# PIC32.net
KiCad netlist of a schematic drawn in Altium Designer
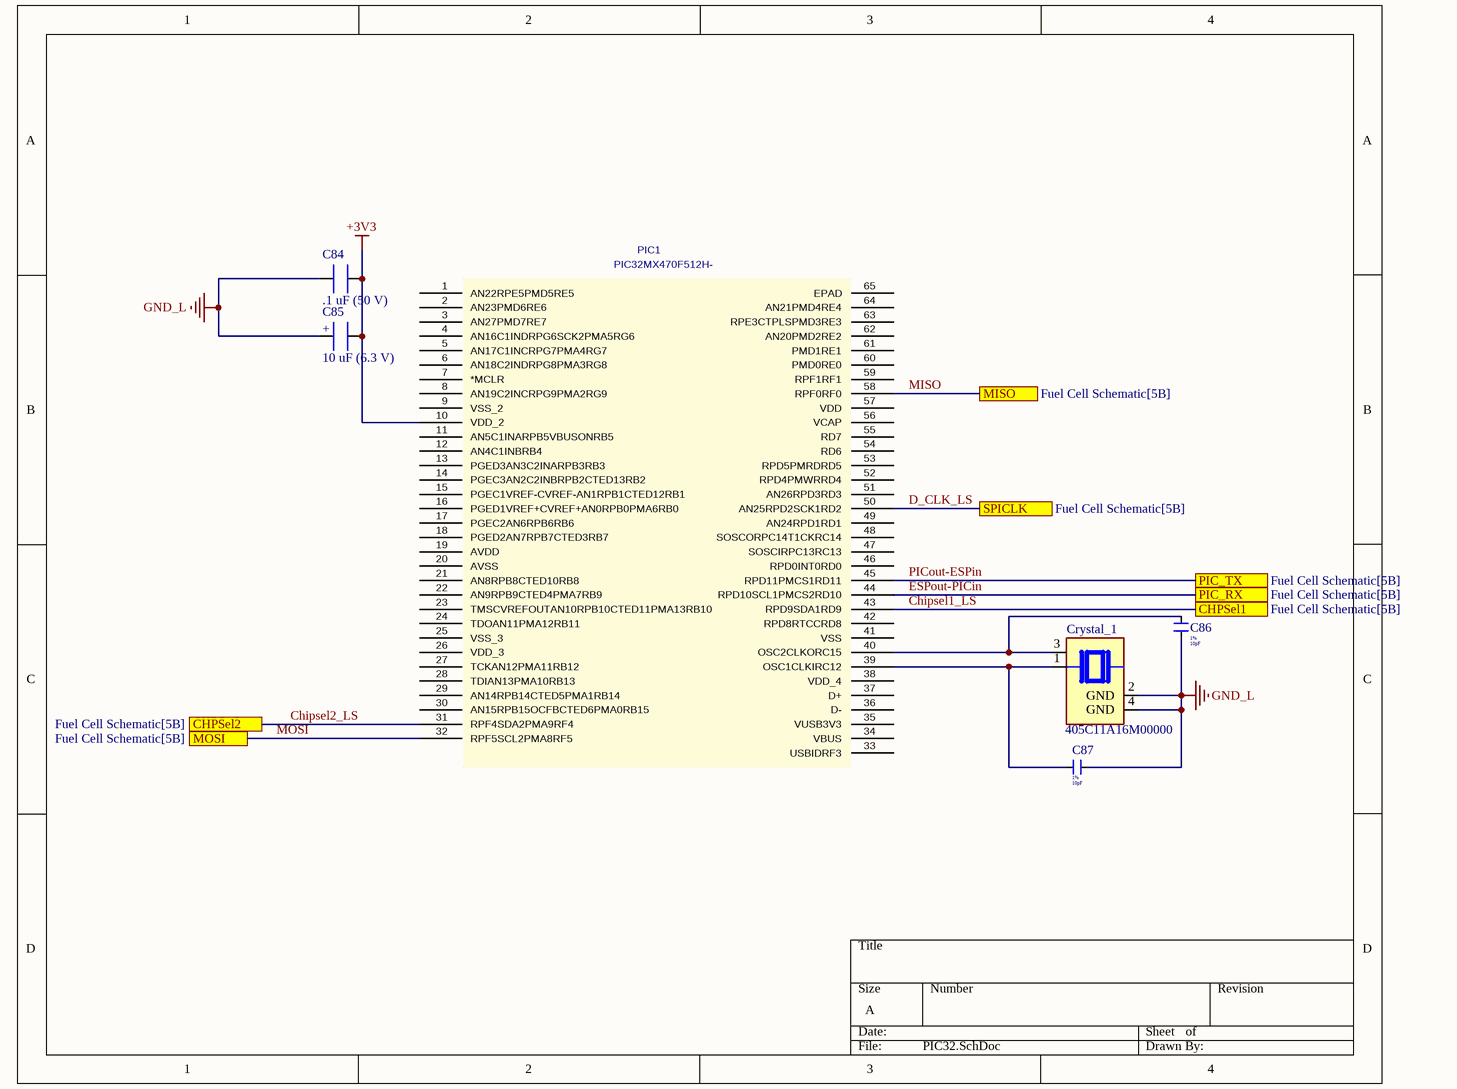
[diagram p0: PIC32.SchDoc]

(export (version "E")
  (design (tool "Eeschema 10.0.6"))
  (components
    (comp (ref "C84")
      (value ".1 uF (50 V)")
      (footprint ".1uF capacitor")
      (libsource (lib "Schlib1") (part ".1 uF cap"))
    )
    (comp (ref "C85")
      (value "10 uF (6.3 V)")
      (footprint "10 uF cap")
      (libsource (lib "Schlib1") (part "10 uF cap"))
    )
    (comp (ref "C86")
      (value "~")
      (footprint "Kemet_10pF_0805")
      (description "Cap, AEC-Q200, 10PF, 50V, Mlcc, 0805;")
      (fields
        (field (name "MANUFACTURER") "KEMET")
        (field (name "MANUFACTURER PART NUMBER") "C0805C100F5GACAUTO")
        (field (name "TOLLERANCE") "1%")
        (field (name "CAPACITANCE") "10pF")
      )
      (libsource (lib "Schlib1") (part "C0805C100F5GACAUTO"))
    )
    (comp (ref "C87")
      (value "~")
      (footprint "Kemet_10pF_0805")
      (description "Cap, AEC-Q200, 10PF, 50V, Mlcc, 0805;")
      (fields
        (field (name "MANUFACTURER") "KEMET")
        (field (name "MANUFACTURER PART NUMBER") "C0805C100F5GACAUTO")
        (field (name "TOLLERANCE") "1%")
        (field (name "CAPACITANCE") "10pF")
      )
      (libsource (lib "Schlib1") (part "C0805C100F5GACAUTO"))
    )
    (comp (ref "Crystal_1")
      (value "405C11A16M00000")
      (footprint "XTAL_405C11A16M00000")
      (description "CRYSTAL 16.0000MHZ 10PF SMD")
      (fields
        (field (name "DIGI-KEY_PART_NUMBER") "CTX834TR-ND")
        (field (name "MF") "CTS-Frequency Controls")
      )
      (libsource (lib "Schlib1") (part "405C11A16M00000"))
    )
    (comp (ref "PIC1")
      (value "PIC32MX470F512H-")
      (footprint "Quad64")
      (fields
        (field (name "MANUFACTURER_PART_NUMBER") "PIC32MX470F512H-I/MR")
        (field (name "COPYRIGHT") "Copyright (C) 2023 Ultra Librarian. All rights reserved.")
      )
      (libsource (lib "Schlib1") (part "PIC32MX470F512H-"))
    )
  )
  (nets
    (net (code "1") (name "+3V3") (class "Default")
      (node (ref "C84") (pin "2") (pinfunction "2_2") (pintype "passive"))
      (node (ref "C85") (pin "2") (pinfunction "2_2") (pintype "passive"))
      (node (ref "PIC1") (pin "10") (pinfunction "VDD_2_10") (pintype "passive"))
    )
    (net (code "2") (name "/Chipsel1_LS") (class "Default")
      (node (ref "PIC1") (pin "43") (pinfunction "RPD9SDA1RD9_43") (pintype "passive"))
    )
    (net (code "3") (name "/Chipsel2_LS") (class "Default")
      (node (ref "PIC1") (pin "31") (pinfunction "RPF4SDA2PMA9RF4_31") (pintype "passive"))
    )
    (net (code "4") (name "/D_CLK_LS") (class "Default")
      (node (ref "PIC1") (pin "50") (pinfunction "AN25RPD2SCK1RD2_50") (pintype "passive"))
    )
    (net (code "5") (name "/ESPout-PICin") (class "Default")
      (node (ref "PIC1") (pin "44") (pinfunction "RPD10SCL1PMCS2RD10_44") (pintype "passive"))
    )
    (net (code "6") (name "/MISO") (class "Default")
      (node (ref "PIC1") (pin "58") (pinfunction "RPF0RF0_58") (pintype "passive"))
    )
    (net (code "7") (name "/MOSI") (class "Default")
      (node (ref "PIC1") (pin "32") (pinfunction "RPF5SCL2PMA8RF5_32") (pintype "passive"))
    )
    (net (code "8") (name "/PICout-ESPin") (class "Default")
      (node (ref "PIC1") (pin "45") (pinfunction "RPD11PMCS1RD11_45") (pintype "passive"))
    )
    (net (code "9") (name "GND_L") (class "Default")
      (node (ref "C84") (pin "1") (pinfunction "1_1") (pintype "passive"))
      (node (ref "C85") (pin "1") (pinfunction "1_1") (pintype "passive"))
      (node (ref "C86") (pin "2") (pinfunction "2_2") (pintype "passive"))
      (node (ref "C87") (pin "1") (pinfunction "1_1") (pintype "passive"))
      (node (ref "Crystal_1") (pin "2") (pinfunction "GND_2") (pintype "power_in"))
      (node (ref "Crystal_1") (pin "4") (pinfunction "GND_4") (pintype "power_in"))
    )
    (net (code "10") (name "Net-(Crystal_1-2)") (class "Default")
      (node (ref "C86") (pin "1") (pinfunction "1_1") (pintype "passive"))
      (node (ref "Crystal_1") (pin "3") (pinfunction "2_3") (pintype "passive"))
      (node (ref "PIC1") (pin "40") (pinfunction "OSC2CLKORC15_40") (pintype "passive"))
    )
    (net (code "11") (name "Net-(PIC1-OSC1CLKIRC12)") (class "Default")
      (node (ref "C87") (pin "2") (pinfunction "2_2") (pintype "passive"))
      (node (ref "Crystal_1") (pin "1") (pinfunction "1_1") (pintype "passive"))
      (node (ref "PIC1") (pin "39") (pinfunction "OSC1CLKIRC12_39") (pintype "passive"))
    )
    (net (code "12") (name "unconnected-(PIC1-*MCLR-Pad7)") (class "Default")
      (node (ref "PIC1") (pin "7") (pinfunction "*MCLR_7") (pintype "passive"))
    )
    (net (code "13") (name "unconnected-(PIC1-AN4C1INBRB4-Pad12)") (class "Default")
      (node (ref "PIC1") (pin "12") (pinfunction "AN4C1INBRB4_12") (pintype "passive"))
    )
    (net (code "14") (name "unconnected-(PIC1-AN5C1INARPB5VBUSONRB5-Pad11)") (class "Default")
      (node (ref "PIC1") (pin "11") (pinfunction "AN5C1INARPB5VBUSONRB5_11") (pintype "passive"))
    )
    (net (code "15") (name "unconnected-(PIC1-AN8RPB8CTED10RB8-Pad21)") (class "Default")
      (node (ref "PIC1") (pin "21") (pinfunction "AN8RPB8CTED10RB8_21") (pintype "passive"))
    )
    (net (code "16") (name "unconnected-(PIC1-AN9RPB9CTED4PMA7RB9-Pad22)") (class "Default")
      (node (ref "PIC1") (pin "22") (pinfunction "AN9RPB9CTED4PMA7RB9_22") (pintype "passive"))
    )
    (net (code "17") (name "unconnected-(PIC1-AN14RPB14CTED5PMA1RB14-Pad29)") (class "Default")
      (node (ref "PIC1") (pin "29") (pinfunction "AN14RPB14CTED5PMA1RB14_29") (pintype "passive"))
    )
    (net (code "18") (name "unconnected-(PIC1-AN15RPB15OCFBCTED6PMA0RB15-Pad30)") (class "Default")
      (node (ref "PIC1") (pin "30") (pinfunction "AN15RPB15OCFBCTED6PMA0RB15_30") (pintype "passive"))
    )
    (net (code "19") (name "unconnected-(PIC1-AN16C1INDRPG6SCK2PMA5RG6-Pad4)") (class "Default")
      (node (ref "PIC1") (pin "4") (pinfunction "AN16C1INDRPG6SCK2PMA5RG6_4") (pintype "passive"))
    )
    (net (code "20") (name "unconnected-(PIC1-AN17C1INCRPG7PMA4RG7-Pad5)") (class "Default")
      (node (ref "PIC1") (pin "5") (pinfunction "AN17C1INCRPG7PMA4RG7_5") (pintype "passive"))
    )
    (net (code "21") (name "unconnected-(PIC1-AN18C2INDRPG8PMA3RG8-Pad6)") (class "Default")
      (node (ref "PIC1") (pin "6") (pinfunction "AN18C2INDRPG8PMA3RG8_6") (pintype "passive"))
    )
    (net (code "22") (name "unconnected-(PIC1-AN19C2INCRPG9PMA2RG9-Pad8)") (class "Default")
      (node (ref "PIC1") (pin "8") (pinfunction "AN19C2INCRPG9PMA2RG9_8") (pintype "passive"))
    )
    (net (code "23") (name "unconnected-(PIC1-AN20PMD2RE2-Pad62)") (class "Default")
      (node (ref "PIC1") (pin "62") (pinfunction "AN20PMD2RE2_62") (pintype "passive"))
    )
    (net (code "24") (name "unconnected-(PIC1-AN21PMD4RE4-Pad64)") (class "Default")
      (node (ref "PIC1") (pin "64") (pinfunction "AN21PMD4RE4_64") (pintype "passive"))
    )
    (net (code "25") (name "unconnected-(PIC1-AN22RPE5PMD5RE5-Pad1)") (class "Default")
      (node (ref "PIC1") (pin "1") (pinfunction "AN22RPE5PMD5RE5_1") (pintype "passive"))
    )
    (net (code "26") (name "unconnected-(PIC1-AN23PMD6RE6-Pad2)") (class "Default")
      (node (ref "PIC1") (pin "2") (pinfunction "AN23PMD6RE6_2") (pintype "passive"))
    )
    (net (code "27") (name "unconnected-(PIC1-AN24RPD1RD1-Pad49)") (class "Default")
      (node (ref "PIC1") (pin "49") (pinfunction "AN24RPD1RD1_49") (pintype "passive"))
    )
    (net (code "28") (name "unconnected-(PIC1-AN26RPD3RD3-Pad51)") (class "Default")
      (node (ref "PIC1") (pin "51") (pinfunction "AN26RPD3RD3_51") (pintype "passive"))
    )
    (net (code "29") (name "unconnected-(PIC1-AN27PMD7RE7-Pad3)") (class "Default")
      (node (ref "PIC1") (pin "3") (pinfunction "AN27PMD7RE7_3") (pintype "passive"))
    )
    (net (code "30") (name "unconnected-(PIC1-AVDD-Pad19)") (class "Default")
      (node (ref "PIC1") (pin "19") (pinfunction "AVDD_19") (pintype "passive"))
    )
    (net (code "31") (name "unconnected-(PIC1-AVSS-Pad20)") (class "Default")
      (node (ref "PIC1") (pin "20") (pinfunction "AVSS_20") (pintype "passive"))
    )
    (net (code "32") (name "unconnected-(PIC1-D+-Pad37)") (class "Default")
      (node (ref "PIC1") (pin "37") (pinfunction "D+_37") (pintype "passive"))
    )
    (net (code "33") (name "unconnected-(PIC1-D--Pad36)") (class "Default")
      (node (ref "PIC1") (pin "36") (pinfunction "D-_36") (pintype "passive"))
    )
    (net (code "34") (name "unconnected-(PIC1-EPAD-Pad65)") (class "Default")
      (node (ref "PIC1") (pin "65") (pinfunction "EPAD_65") (pintype "passive"))
    )
    (net (code "35") (name "unconnected-(PIC1-PGEC1VREF-CVREF-AN1RPB1CTED12RB1-Pad15)") (class "Default")
      (node (ref "PIC1") (pin "15") (pinfunction "PGEC1VREF-CVREF-AN1RPB1CTED12RB1_15") (pintype "passive"))
    )
    (net (code "36") (name "unconnected-(PIC1-PGEC2AN6RPB6RB6-Pad17)") (class "Default")
      (node (ref "PIC1") (pin "17") (pinfunction "PGEC2AN6RPB6RB6_17") (pintype "passive"))
    )
    (net (code "37") (name "unconnected-(PIC1-PGEC3AN2C2INBRPB2CTED13RB2-Pad14)") (class "Default")
      (node (ref "PIC1") (pin "14") (pinfunction "PGEC3AN2C2INBRPB2CTED13RB2_14") (pintype "passive"))
    )
    (net (code "38") (name "unconnected-(PIC1-PGED1VREF+CVREF+AN0RPB0PMA6RB0-Pad16)") (class "Default")
      (node (ref "PIC1") (pin "16") (pinfunction "PGED1VREF+CVREF+AN0RPB0PMA6RB0_16") (pintype "passive"))
    )
    (net (code "39") (name "unconnected-(PIC1-PGED2AN7RPB7CTED3RB7-Pad18)") (class "Default")
      (node (ref "PIC1") (pin "18") (pinfunction "PGED2AN7RPB7CTED3RB7_18") (pintype "passive"))
    )
    (net (code "40") (name "unconnected-(PIC1-PGED3AN3C2INARPB3RB3-Pad13)") (class "Default")
      (node (ref "PIC1") (pin "13") (pinfunction "PGED3AN3C2INARPB3RB3_13") (pintype "passive"))
    )
    (net (code "41") (name "unconnected-(PIC1-PMD0RE0-Pad60)") (class "Default")
      (node (ref "PIC1") (pin "60") (pinfunction "PMD0RE0_60") (pintype "passive"))
    )
    (net (code "42") (name "unconnected-(PIC1-PMD1RE1-Pad61)") (class "Default")
      (node (ref "PIC1") (pin "61") (pinfunction "PMD1RE1_61") (pintype "passive"))
    )
    (net (code "43") (name "unconnected-(PIC1-RD6-Pad54)") (class "Default")
      (node (ref "PIC1") (pin "54") (pinfunction "RD6_54") (pintype "passive"))
    )
    (net (code "44") (name "unconnected-(PIC1-RD7-Pad55)") (class "Default")
      (node (ref "PIC1") (pin "55") (pinfunction "RD7_55") (pintype "passive"))
    )
    (net (code "45") (name "unconnected-(PIC1-RPD0INT0RD0-Pad46)") (class "Default")
      (node (ref "PIC1") (pin "46") (pinfunction "RPD0INT0RD0_46") (pintype "passive"))
    )
    (net (code "46") (name "unconnected-(PIC1-RPD4PMWRRD4-Pad52)") (class "Default")
      (node (ref "PIC1") (pin "52") (pinfunction "RPD4PMWRRD4_52") (pintype "passive"))
    )
    (net (code "47") (name "unconnected-(PIC1-RPD5PMRDRD5-Pad53)") (class "Default")
      (node (ref "PIC1") (pin "53") (pinfunction "RPD5PMRDRD5_53") (pintype "passive"))
    )
    (net (code "48") (name "unconnected-(PIC1-RPD8RTCCRD8-Pad42)") (class "Default")
      (node (ref "PIC1") (pin "42") (pinfunction "RPD8RTCCRD8_42") (pintype "passive"))
    )
    (net (code "49") (name "unconnected-(PIC1-RPE3CTPLSPMD3RE3-Pad63)") (class "Default")
      (node (ref "PIC1") (pin "63") (pinfunction "RPE3CTPLSPMD3RE3_63") (pintype "passive"))
    )
    (net (code "50") (name "unconnected-(PIC1-RPF1RF1-Pad59)") (class "Default")
      (node (ref "PIC1") (pin "59") (pinfunction "RPF1RF1_59") (pintype "passive"))
    )
    (net (code "51") (name "unconnected-(PIC1-SOSCIRPC13RC13-Pad47)") (class "Default")
      (node (ref "PIC1") (pin "47") (pinfunction "SOSCIRPC13RC13_47") (pintype "passive"))
    )
    (net (code "52") (name "unconnected-(PIC1-SOSCORPC14T1CKRC14-Pad48)") (class "Default")
      (node (ref "PIC1") (pin "48") (pinfunction "SOSCORPC14T1CKRC14_48") (pintype "passive"))
    )
    (net (code "53") (name "unconnected-(PIC1-TCKAN12PMA11RB12-Pad27)") (class "Default")
      (node (ref "PIC1") (pin "27") (pinfunction "TCKAN12PMA11RB12_27") (pintype "passive"))
    )
    (net (code "54") (name "unconnected-(PIC1-TDIAN13PMA10RB13-Pad28)") (class "Default")
      (node (ref "PIC1") (pin "28") (pinfunction "TDIAN13PMA10RB13_28") (pintype "passive"))
    )
    (net (code "55") (name "unconnected-(PIC1-TDOAN11PMA12RB11-Pad24)") (class "Default")
      (node (ref "PIC1") (pin "24") (pinfunction "TDOAN11PMA12RB11_24") (pintype "passive"))
    )
    (net (code "56") (name "unconnected-(PIC1-TMSCVREFOUTAN10RPB10CTED11PMA13RB10-Pad23)") (class "Default")
      (node (ref "PIC1") (pin "23") (pinfunction "TMSCVREFOUTAN10RPB10CTED11PMA13RB10_23") (pintype "passive"))
    )
    (net (code "57") (name "unconnected-(PIC1-USBIDRF3-Pad33)") (class "Default")
      (node (ref "PIC1") (pin "33") (pinfunction "USBIDRF3_33") (pintype "passive"))
    )
    (net (code "58") (name "unconnected-(PIC1-VBUS-Pad34)") (class "Default")
      (node (ref "PIC1") (pin "34") (pinfunction "VBUS_34") (pintype "passive"))
    )
    (net (code "59") (name "unconnected-(PIC1-VCAP-Pad56)") (class "Default")
      (node (ref "PIC1") (pin "56") (pinfunction "VCAP_56") (pintype "passive"))
    )
    (net (code "60") (name "unconnected-(PIC1-VDD-Pad57)") (class "Default")
      (node (ref "PIC1") (pin "57") (pinfunction "VDD_57") (pintype "passive"))
    )
    (net (code "61") (name "unconnected-(PIC1-VDD_3-Pad26)") (class "Default")
      (node (ref "PIC1") (pin "26") (pinfunction "VDD_3_26") (pintype "passive"))
    )
    (net (code "62") (name "unconnected-(PIC1-VDD_4-Pad38)") (class "Default")
      (node (ref "PIC1") (pin "38") (pinfunction "VDD_4_38") (pintype "passive"))
    )
    (net (code "63") (name "unconnected-(PIC1-VSS-Pad41)") (class "Default")
      (node (ref "PIC1") (pin "41") (pinfunction "VSS_41") (pintype "passive"))
    )
    (net (code "64") (name "unconnected-(PIC1-VSS_2-Pad9)") (class "Default")
      (node (ref "PIC1") (pin "9") (pinfunction "VSS_2_9") (pintype "passive"))
    )
    (net (code "65") (name "unconnected-(PIC1-VSS_3-Pad25)") (class "Default")
      (node (ref "PIC1") (pin "25") (pinfunction "VSS_3_25") (pintype "passive"))
    )
    (net (code "66") (name "unconnected-(PIC1-VUSB3V3-Pad35)") (class "Default")
      (node (ref "PIC1") (pin "35") (pinfunction "VUSB3V3_35") (pintype "passive"))
    )
  )
)
